# 01_GAP9_INTERFACE.net
KiCad netlist of a schematic drawn in Altium Designer
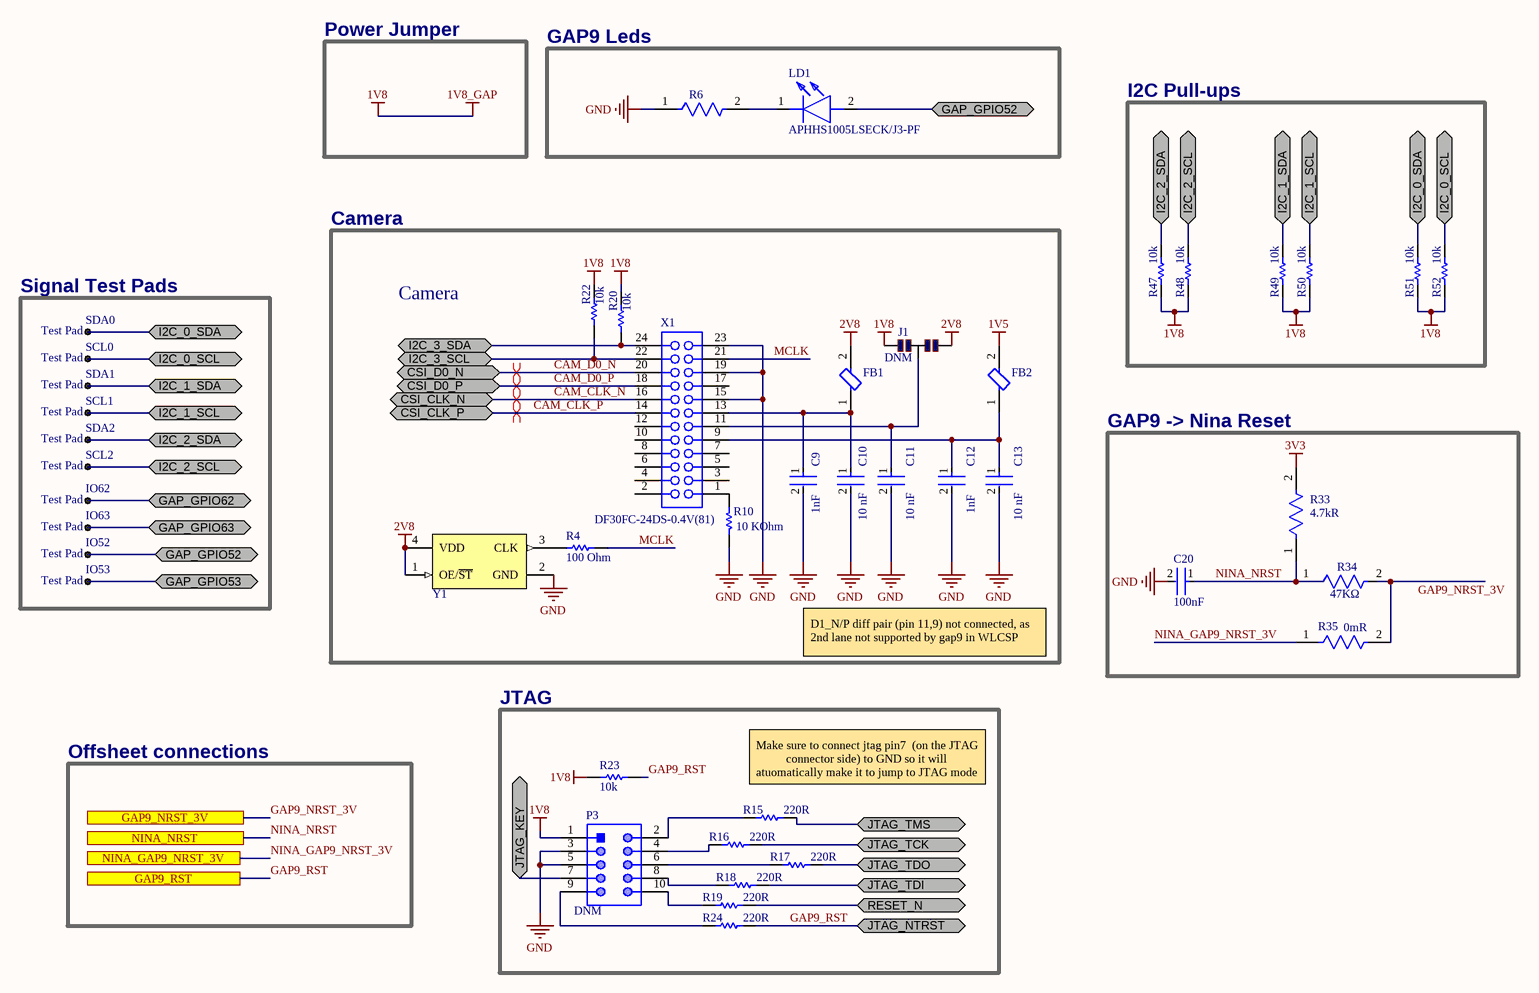
[diagram p0: 01_GAP9_INTERFACE.SchDoc]

(export (version "E")
  (design (tool "Eeschema 10.0.6"))
  (components
    (comp (ref "C9")
      (value "1nF")
      (footprint "FP-GRM155-0_05-IPC_B")
      (description "Chip Multilayer Ceramic Capacitors for General Purpose, 0402, 1000pF, C0G, 30ppm/°C, 5%, 50V")
      (fields (field (name "TOLERANCE") "5%") (field (name "VOLTAGE") "50V"))
      (libsource (lib "Altium Content Vault") (part "02cd4be3c70576c341d710602a673aa"))
    )
    (comp (ref "C10")
      (value "CC0402KRX7R7BB103")
      (footprint "FP-CC0402-MFG")
      (description "CAP CER 10000PF 16V X7R 0402")
      (fields
        (field (name "CAPACITANCE") "10 nF")
        (field (name "TOLERANCE") "0.1")
        (field (name "MANUFACTURER") "YAGEO")
      )
      (libsource (lib "Altium Content Vault") (part "11868f565c42a9108669ba33697ecf6"))
    )
    (comp (ref "C11")
      (value "CC0402KRX7R7BB103")
      (footprint "FP-CC0402-MFG")
      (description "CAP CER 10000PF 16V X7R 0402")
      (fields
        (field (name "CAPACITANCE") "10 nF")
        (field (name "TOLERANCE") "0.1")
        (field (name "MANUFACTURER") "YAGEO")
      )
      (libsource (lib "Altium Content Vault") (part "11868f565c42a9108669ba33697ecf6"))
    )
    (comp (ref "C12")
      (value "1nF")
      (footprint "FP-GRM155-0_05-IPC_B")
      (description "Chip Multilayer Ceramic Capacitors for General Purpose, 0402, 1000pF, C0G, 30ppm/°C, 5%, 50V")
      (fields (field (name "TOLERANCE") "5%") (field (name "VOLTAGE") "50V"))
      (libsource (lib "Altium Content Vault") (part "02cd4be3c70576c341d710602a673aa"))
    )
    (comp (ref "C13")
      (value "CC0402KRX7R7BB103")
      (footprint "FP-CC0402-MFG")
      (description "CAP CER 10000PF 16V X7R 0402")
      (fields
        (field (name "CAPACITANCE") "10 nF")
        (field (name "TOLERANCE") "0.1")
        (field (name "MANUFACTURER") "YAGEO")
      )
      (libsource (lib "Altium Content Vault") (part "11868f565c42a9108669ba33697ecf6"))
    )
    (comp (ref "C20")
      (value "100nF")
      (footprint "FP-C1005-050-0_05-MFG")
      (description "Multilayer Ceramic Capacitors 100nF ±10% 25V X5R SMD 0402")
      (fields (field (name "TOLERANCE") "10%") (field (name "VOLTAGE") "25V"))
      (libsource (lib "Altium Content Vault") (part "b4654b650e69147ec39a6b967a45e02"))
    )
    (comp (ref "FB1")
      (value "BLM18HE152SN1D")
      (footprint "FP-BLM18-0_15-t0_8-IPC_C")
      (description "Chip Ferrite Bead, 0603, 1500Ω @ 100MHz, 0.5Ω, 25%, 500mA")
      (fields (field (name "TOLERANCE") "25%"))
      (libsource (lib "Altium Content Vault") (part "5f30dd21d616792df468990f7003faa"))
    )
    (comp (ref "FB2")
      (value "BLM18HE152SN1D")
      (footprint "FP-BLM18-0_15-t0_8-IPC_C")
      (description "Chip Ferrite Bead, 0603, 1500Ω @ 100MHz, 0.5Ω, 25%, 500mA")
      (fields (field (name "TOLERANCE") "25%"))
      (libsource (lib "Altium Content Vault") (part "5f30dd21d616792df468990f7003faa"))
    )
    (comp (ref "IO52")
      (value "Test Pad")
      (footprint "Pad-1.5mm")
      (description "1mm SMT Test Pad")
      (libsource (lib "gap9_deck") (part "CMP-01283-1"))
    )
    (comp (ref "IO53")
      (value "Test Pad")
      (footprint "Pad-1.5mm")
      (description "1mm SMT Test Pad")
      (libsource (lib "gap9_deck") (part "CMP-01283-1"))
    )
    (comp (ref "IO62")
      (value "Test Pad")
      (footprint "Pad-1.5mm")
      (description "1mm SMT Test Pad")
      (libsource (lib "gap9_deck") (part "CMP-01283-1"))
    )
    (comp (ref "IO63")
      (value "Test Pad")
      (footprint "Pad-1.5mm")
      (description "1mm SMT Test Pad")
      (libsource (lib "gap9_deck") (part "CMP-01283-1"))
    )
    (comp (ref "J1")
      (value "DNM")
      (footprint "Jumper 3 pins")
      (description "Solder Jumper 3 Pads")
      (libsource (lib "ETHZ Vault") (part "Solder Jumper 3-pads"))
    )
    (comp (ref "LD1")
      (value "APHHS1005LSECK/J3-PF")
      (footprint "SamacSys:APHHS1005LSECKJ3PF")
      (description "LED")
      (fields (field (name "MOUSER PART NUMBER") "604-APHHS1005LSECKJ3"))
      (libsource (lib "*") (part "APHHS1005LSECK_J3-PF"))
    )
    (comp (ref "P3")
      (value "DNM")
      (footprint "Crazyflie:2x10Pin_Horizontal_50mil")
      (description "2x10 Pin 50mil Header")
      (libsource (lib "Crazyflie") (part "CF_JTAG_Header"))
    )
    (comp (ref "R4")
      (value "100 Ohm")
      (footprint "RESC1005X40X25LL05T05")
      (description "Chip Resistor, 100 Ohm, +/- 1%, 100 mW, -55 to 155 degC, 0402 (1005 Metric), RoHS, Tape and Reel")
      (fields (field (name "MANUFACTURER") "Basic Passives") (field (name "TOLERANCE") "1%"))
      (libsource (lib "Altium Content Vault") (part "RES-2"))
    )
    (comp (ref "R6")
      (value "RC0201JR-070RL")
      (footprint "FP-RC_L0201-MFG")
      (description "RES SMD 0 OHM JUMPER 1/20W 0201")
      (fields
        (field (name "OCTOPART") "https://octopart.com/rc0201jr-070rl-yageo-43171986")
        (field (name "MANUFACTURER") "Yageo")
      )
      (libsource (lib "Altium Content Vault") (part "1029c3af85768c4190bb7ad29bc67b5"))
    )
    (comp (ref "R10")
      (value "10 KOhm")
      (footprint "RESC1005X40X25NL05T05")
      (description "Chip Resistor, 10 KOhm, +/- 1%, 100 mW, -55 to 155 degC, 0402 (1005 Metric), RoHS, Tape and Reel")
      (fields (field (name "MANUFACTURER") "Basic Passives") (field (name "TOLERANCE") "1%"))
      (libsource (lib "Altium Content Vault") (part "CMP-2002-00607-3"))
    )
    (comp (ref "R15")
      (value "220R")
      (footprint "RESC0603X28X15ML05T05")
      (fields (field (name "MANUFACTURER") "Vishay Dale") (field (name "PART NUMBER") "CRCW0201220RFKED"))
      (libsource (lib "Altium Content Vault") (part "RES"))
    )
    (comp (ref "R16")
      (value "220R")
      (footprint "RESC0603X28X15ML05T05")
      (fields (field (name "MANUFACTURER") "Vishay Dale") (field (name "PART NUMBER") "CRCW0201220RFKED"))
      (libsource (lib "Altium Content Vault") (part "RES"))
    )
    (comp (ref "R17")
      (value "220R")
      (footprint "RESC0603X28X15ML05T05")
      (fields (field (name "MANUFACTURER") "Vishay Dale") (field (name "PART NUMBER") "CRCW0201220RFKED"))
      (libsource (lib "Altium Content Vault") (part "RES"))
    )
    (comp (ref "R18")
      (value "220R")
      (footprint "RESC0603X28X15ML05T05")
      (fields (field (name "MANUFACTURER") "Vishay Dale") (field (name "PART NUMBER") "CRCW0201220RFKED"))
      (libsource (lib "Altium Content Vault") (part "RES"))
    )
    (comp (ref "R19")
      (value "220R")
      (footprint "RESC0603X28X15ML05T05")
      (fields (field (name "MANUFACTURER") "Vishay Dale") (field (name "PART NUMBER") "CRCW0201220RFKED"))
      (libsource (lib "Altium Content Vault") (part "RES"))
    )
    (comp (ref "R20")
      (value "10k")
      (footprint "RESC0603X28X15LL05T05")
      (fields (field (name "MANUFACTURER") "Vishay Dale") (field (name "PART NUMBER") "CRCW020110K0FNED"))
      (libsource (lib "Altium Content Vault") (part "RES"))
    )
    (comp (ref "R22")
      (value "10k")
      (footprint "RESC0603X28X15LL05T05")
      (fields (field (name "MANUFACTURER") "Vishay Dale") (field (name "PART NUMBER") "CRCW020110K0FNED"))
      (libsource (lib "Altium Content Vault") (part "RES"))
    )
    (comp (ref "R23")
      (value "10k")
      (footprint "RESC0603X28X15LL05T05")
      (fields (field (name "MANUFACTURER") "Vishay Dale") (field (name "PART NUMBER") "CRCW020110K0FNED"))
      (libsource (lib "Altium Content Vault") (part "RES"))
    )
    (comp (ref "R24")
      (value "220R")
      (footprint "RESC0603X28X15ML05T05")
      (fields (field (name "MANUFACTURER") "Vishay Dale") (field (name "PART NUMBER") "CRCW0201220RFKED"))
      (libsource (lib "Altium Content Vault") (part "RES"))
    )
    (comp (ref "R33")
      (value "4.7kR")
      (footprint "FP-CRCW0402-e3-IPC_B")
      (description "RES Thick Film, 4.7kΩ, 1%, 0.063W, 100ppm/°C, 0402")
      (fields (field (name "TOLERANCE") "1%") (field (name "Comment") "CRCW04024K70FKED"))
      (libsource (lib "Altium Content Vault") (part "1029c3af85768c4190bb7ad29bc67b5"))
    )
    (comp (ref "R34")
      (value "47KΩ")
      (footprint "FP-CRGCQ0402-IPC_C")
      (description "CRGCQ0402 47KΩ 1% ±100ppm/°C 50V")
      (fields
        (field (name "OCTOPART") "https://octopart.com/crgcq0402f47k-te+connectivity-91017973")
        (field (name "TOLERANCE") "0.01")
      )
      (libsource (lib "Altium Content Vault") (part "1029c3af85768c4190bb7ad29bc67b5"))
    )
    (comp (ref "R35")
      (value "0mR")
      (footprint "FP-CRCW0402-e3-IPC_C")
      (description "RES Thick Film, 0Ω, 0.063W, 0402")
      (fields (field (name "TOLERANCE") "5%") (field (name "Comment") "CRCW04020000Z0ED"))
      (libsource (lib "Altium Content Vault") (part "1029c3af85768c4190bb7ad29bc67b5"))
    )
    (comp (ref "R47")
      (value "10k")
      (footprint "RESC0603X28X15LL05T05")
      (fields (field (name "MANUFACTURER") "Vishay Dale") (field (name "PART NUMBER") "CRCW020110K0FNED"))
      (libsource (lib "Altium Content Vault") (part "RES"))
    )
    (comp (ref "R48")
      (value "10k")
      (footprint "RESC0603X28X15LL05T05")
      (fields (field (name "MANUFACTURER") "Vishay Dale") (field (name "PART NUMBER") "CRCW020110K0FNED"))
      (libsource (lib "Altium Content Vault") (part "RES"))
    )
    (comp (ref "R49")
      (value "10k")
      (footprint "RESC0603X28X15LL05T05")
      (fields (field (name "MANUFACTURER") "Vishay Dale") (field (name "PART NUMBER") "CRCW020110K0FNED"))
      (libsource (lib "Altium Content Vault") (part "RES"))
    )
    (comp (ref "R50")
      (value "10k")
      (footprint "RESC0603X28X15LL05T05")
      (fields (field (name "MANUFACTURER") "Vishay Dale") (field (name "PART NUMBER") "CRCW020110K0FNED"))
      (libsource (lib "Altium Content Vault") (part "RES"))
    )
    (comp (ref "R51")
      (value "10k")
      (footprint "RESC0603X28X15LL05T05")
      (fields (field (name "MANUFACTURER") "Vishay Dale") (field (name "PART NUMBER") "CRCW020110K0FNED"))
      (libsource (lib "Altium Content Vault") (part "RES"))
    )
    (comp (ref "R52")
      (value "10k")
      (footprint "RESC0603X28X15LL05T05")
      (fields (field (name "MANUFACTURER") "Vishay Dale") (field (name "PART NUMBER") "CRCW020110K0FNED"))
      (libsource (lib "Altium Content Vault") (part "RES"))
    )
    (comp (ref "SCL0")
      (value "Test Pad")
      (footprint "Pad-1.5mm")
      (description "1mm SMT Test Pad")
      (libsource (lib "gap9_deck") (part "CMP-01283-1"))
    )
    (comp (ref "SCL1")
      (value "Test Pad")
      (footprint "Pad-1.5mm")
      (description "1mm SMT Test Pad")
      (libsource (lib "gap9_deck") (part "CMP-01283-1"))
    )
    (comp (ref "SCL2")
      (value "Test Pad")
      (footprint "Pad-1.5mm")
      (description "1mm SMT Test Pad")
      (libsource (lib "gap9_deck") (part "CMP-01283-1"))
    )
    (comp (ref "SDA0")
      (value "Test Pad")
      (footprint "Pad-1.5mm")
      (description "1mm SMT Test Pad")
      (libsource (lib "gap9_deck") (part "CMP-01283-1"))
    )
    (comp (ref "SDA1")
      (value "Test Pad")
      (footprint "Pad-1.5mm")
      (description "1mm SMT Test Pad")
      (libsource (lib "gap9_deck") (part "CMP-01283-1"))
    )
    (comp (ref "SDA2")
      (value "Test Pad")
      (footprint "Pad-1.5mm")
      (description "1mm SMT Test Pad")
      (libsource (lib "gap9_deck") (part "CMP-01283-1"))
    )
    (comp (ref "X1")
      (value "DF30FC-24DS-0.4V(81)")
      (footprint "DF30FC-24DS-0.4V(81)")
      (libsource (lib "ETHZ Vault") (part "CON-2x12-Female"))
    )
    (comp (ref "Y1")
      (value "KC2520K25.0000C1GE00")
      (footprint "AB-24.000MAGE-T")
      (description "OSCILLATOR XO 25.000MHZ CMOS SMD")
      (fields (field (name "MANUFACTURER") "AVX-Corp-Kyocera-Corp"))
      (libsource (lib "altium-import") (part "root_0_SiT8008_"))
    )
  )
  (nets
    (net (code "1") (name "/CAM_CLK_N") (class "Default")
      (node (ref "X1") (pin "16") (pinfunction "16_16") (pintype "passive"))
    )
    (net (code "2") (name "/CAM_CLK_P") (class "Default")
      (node (ref "X1") (pin "14") (pinfunction "14_14") (pintype "passive"))
    )
    (net (code "3") (name "/CAM_D0_N") (class "Default")
      (node (ref "X1") (pin "20") (pinfunction "20_20") (pintype "passive"))
    )
    (net (code "4") (name "/CAM_D0_P") (class "Default")
      (node (ref "X1") (pin "18") (pinfunction "18_18") (pintype "passive"))
    )
    (net (code "5") (name "/GAP9_NRST_3V") (class "Default")
      (node (ref "R34") (pin "2") (pinfunction "2_2") (pintype "passive"))
      (node (ref "R35") (pin "2") (pinfunction "2_2") (pintype "passive"))
    )
    (net (code "6") (name "/GAP9_RST") (class "Default")
      (node (ref "R23") (pin "2") (pinfunction "2_2") (pintype "passive"))
      (node (ref "R24") (pin "2") (pinfunction "2_2") (pintype "passive"))
    )
    (net (code "7") (name "/GAP_GPIO52") (class "Default")
      (node (ref "IO52") (pin "1") (pinfunction "1_1") (pintype "passive"))
      (node (ref "LD1") (pin "2") (pinfunction "A_2") (pintype "passive"))
    )
    (net (code "8") (name "/GAP_GPIO53") (class "Default")
      (node (ref "IO53") (pin "1") (pinfunction "1_1") (pintype "passive"))
    )
    (net (code "9") (name "/GAP_GPIO62") (class "Default")
      (node (ref "IO62") (pin "1") (pinfunction "1_1") (pintype "passive"))
    )
    (net (code "10") (name "/GAP_GPIO63") (class "Default")
      (node (ref "IO63") (pin "1") (pinfunction "1_1") (pintype "passive"))
    )
    (net (code "11") (name "/I2C_0_SCL") (class "Default")
      (node (ref "R52") (pin "2") (pinfunction "2_2") (pintype "passive"))
      (node (ref "SCL0") (pin "1") (pinfunction "1_1") (pintype "passive"))
    )
    (net (code "12") (name "/I2C_0_SDA") (class "Default")
      (node (ref "R51") (pin "2") (pinfunction "2_2") (pintype "passive"))
      (node (ref "SDA0") (pin "1") (pinfunction "1_1") (pintype "passive"))
    )
    (net (code "13") (name "/I2C_1_SCL") (class "Default")
      (node (ref "R50") (pin "2") (pinfunction "2_2") (pintype "passive"))
      (node (ref "SCL1") (pin "1") (pinfunction "1_1") (pintype "passive"))
    )
    (net (code "14") (name "/I2C_1_SDA") (class "Default")
      (node (ref "R49") (pin "2") (pinfunction "2_2") (pintype "passive"))
      (node (ref "SDA1") (pin "1") (pinfunction "1_1") (pintype "passive"))
    )
    (net (code "15") (name "/I2C_2_SCL") (class "Default")
      (node (ref "R48") (pin "2") (pinfunction "2_2") (pintype "passive"))
      (node (ref "SCL2") (pin "1") (pinfunction "1_1") (pintype "passive"))
    )
    (net (code "16") (name "/I2C_2_SDA") (class "Default")
      (node (ref "R47") (pin "2") (pinfunction "2_2") (pintype "passive"))
      (node (ref "SDA2") (pin "1") (pinfunction "1_1") (pintype "passive"))
    )
    (net (code "17") (name "/I2C_3_SCL") (class "Default")
      (node (ref "R22") (pin "1") (pinfunction "1_1") (pintype "passive"))
      (node (ref "X1") (pin "22") (pinfunction "22_22") (pintype "passive"))
    )
    (net (code "18") (name "/I2C_3_SDA") (class "Default")
      (node (ref "R20") (pin "1") (pinfunction "1_1") (pintype "passive"))
      (node (ref "X1") (pin "24") (pinfunction "24_24") (pintype "passive"))
    )
    (net (code "19") (name "/JTAG_KEY") (class "Default")
      (node (ref "P3") (pin "7") (pinfunction "7_7") (pintype "passive"))
    )
    (net (code "20") (name "/JTAG_TCK") (class "Default")
      (node (ref "R16") (pin "2") (pinfunction "2_2") (pintype "passive"))
    )
    (net (code "21") (name "/JTAG_TDI") (class "Default")
      (node (ref "R18") (pin "2") (pinfunction "2_2") (pintype "passive"))
    )
    (net (code "22") (name "/JTAG_TDO") (class "Default")
      (node (ref "R17") (pin "2") (pinfunction "2_2") (pintype "passive"))
    )
    (net (code "23") (name "/JTAG_TMS") (class "Default")
      (node (ref "R15") (pin "2") (pinfunction "2_2") (pintype "passive"))
    )
    (net (code "24") (name "/MCLK") (class "Default")
      (node (ref "R4") (pin "1") (pinfunction "1_1") (pintype "passive"))
      (node (ref "X1") (pin "21") (pinfunction "21_21") (pintype "passive"))
    )
    (net (code "25") (name "/NINA_GAP9_NRST_3V") (class "Default")
      (node (ref "R35") (pin "1") (pinfunction "1_1") (pintype "passive"))
    )
    (net (code "26") (name "/NINA_NRST") (class "Default")
      (node (ref "C20") (pin "1") (pinfunction "1_1") (pintype "passive"))
      (node (ref "R33") (pin "1") (pinfunction "1_1") (pintype "passive"))
      (node (ref "R34") (pin "1") (pinfunction "1_1") (pintype "passive"))
    )
    (net (code "27") (name "/RESET_N") (class "Default")
      (node (ref "R19") (pin "2") (pinfunction "2_2") (pintype "passive"))
    )
    (net (code "28") (name "1V5") (class "Default")
      (node (ref "FB2") (pin "2") (pinfunction "2_2") (pintype "passive"))
    )
    (net (code "29") (name "1V8") (class "Default")
      (node (ref "J1") (pin "1") (pinfunction "1_1") (pintype "passive"))
      (node (ref "P3") (pin "1") (pinfunction "1_1") (pintype "passive"))
      (node (ref "R20") (pin "2") (pinfunction "2_2") (pintype "passive"))
      (node (ref "R22") (pin "2") (pinfunction "2_2") (pintype "passive"))
      (node (ref "R23") (pin "1") (pinfunction "1_1") (pintype "passive"))
      (node (ref "R47") (pin "1") (pinfunction "1_1") (pintype "passive"))
      (node (ref "R48") (pin "1") (pinfunction "1_1") (pintype "passive"))
      (node (ref "R49") (pin "1") (pinfunction "1_1") (pintype "passive"))
      (node (ref "R50") (pin "1") (pinfunction "1_1") (pintype "passive"))
      (node (ref "R51") (pin "1") (pinfunction "1_1") (pintype "passive"))
      (node (ref "R52") (pin "1") (pinfunction "1_1") (pintype "passive"))
    )
    (net (code "30") (name "2V8") (class "Default")
      (node (ref "FB1") (pin "2") (pinfunction "2_2") (pintype "passive"))
      (node (ref "J1") (pin "3") (pinfunction "3_3") (pintype "passive"))
      (node (ref "Y1") (pin "1") (pinfunction "OE/~{ST}_1") (pintype "input"))
      (node (ref "Y1") (pin "4") (pinfunction "VDD_4") (pintype "power_in"))
    )
    (net (code "31") (name "3V3") (class "Default")
      (node (ref "R33") (pin "2") (pinfunction "2_2") (pintype "passive"))
    )
    (net (code "32") (name "GND") (class "Default")
      (node (ref "C10") (pin "2") (pinfunction "2_2") (pintype "passive"))
      (node (ref "C11") (pin "2") (pinfunction "2_2") (pintype "passive"))
      (node (ref "C12") (pin "2") (pinfunction "2_2") (pintype "passive"))
      (node (ref "C13") (pin "2") (pinfunction "2_2") (pintype "passive"))
      (node (ref "C20") (pin "2") (pinfunction "2_2") (pintype "passive"))
      (node (ref "C9") (pin "2") (pinfunction "2_2") (pintype "passive"))
      (node (ref "P3") (pin "3") (pinfunction "3_3") (pintype "passive"))
      (node (ref "P3") (pin "5") (pinfunction "5_5") (pintype "passive"))
      (node (ref "R10") (pin "2") (pinfunction "2_2") (pintype "passive"))
      (node (ref "R6") (pin "1") (pinfunction "1_1") (pintype "passive"))
      (node (ref "X1") (pin "15") (pinfunction "15_15") (pintype "passive"))
      (node (ref "X1") (pin "19") (pinfunction "19_19") (pintype "passive"))
      (node (ref "X1") (pin "23") (pinfunction "23_23") (pintype "passive"))
      (node (ref "Y1") (pin "2") (pinfunction "GND_2") (pintype "power_in"))
    )
    (net (code "33") (name "Net-(C10-Pad1)") (class "Default")
      (node (ref "C10") (pin "1") (pinfunction "1_1") (pintype "passive"))
      (node (ref "C9") (pin "1") (pinfunction "1_1") (pintype "passive"))
      (node (ref "FB1") (pin "1") (pinfunction "1_1") (pintype "passive"))
      (node (ref "X1") (pin "13") (pinfunction "13_13") (pintype "passive"))
    )
    (net (code "34") (name "Net-(C11-Pad1)") (class "Default")
      (node (ref "C11") (pin "1") (pinfunction "1_1") (pintype "passive"))
      (node (ref "J1") (pin "2") (pinfunction "2_2") (pintype "passive"))
      (node (ref "X1") (pin "11") (pinfunction "11_11") (pintype "passive"))
    )
    (net (code "35") (name "Net-(C12-Pad1)") (class "Default")
      (node (ref "C12") (pin "1") (pinfunction "1_1") (pintype "passive"))
      (node (ref "C13") (pin "1") (pinfunction "1_1") (pintype "passive"))
      (node (ref "FB2") (pin "1") (pinfunction "1_1") (pintype "passive"))
      (node (ref "X1") (pin "9") (pinfunction "9_9") (pintype "passive"))
    )
    (net (code "36") (name "Net-(LD1-K)") (class "Default")
      (node (ref "LD1") (pin "1") (pinfunction "K_1") (pintype "passive"))
      (node (ref "R6") (pin "2") (pinfunction "2_2") (pintype "passive"))
    )
    (net (code "37") (name "Net-(P3-Pad2)") (class "Default")
      (node (ref "P3") (pin "2") (pinfunction "2_2") (pintype "passive"))
      (node (ref "R15") (pin "1") (pinfunction "1_1") (pintype "passive"))
    )
    (net (code "38") (name "Net-(P3-Pad4)") (class "Default")
      (node (ref "P3") (pin "4") (pinfunction "4_4") (pintype "passive"))
      (node (ref "R16") (pin "1") (pinfunction "1_1") (pintype "passive"))
    )
    (net (code "39") (name "Net-(P3-Pad6)") (class "Default")
      (node (ref "P3") (pin "6") (pinfunction "6_6") (pintype "passive"))
      (node (ref "R17") (pin "1") (pinfunction "1_1") (pintype "passive"))
    )
    (net (code "40") (name "Net-(P3-Pad8)") (class "Default")
      (node (ref "P3") (pin "8") (pinfunction "8_8") (pintype "passive"))
      (node (ref "R18") (pin "1") (pinfunction "1_1") (pintype "passive"))
    )
    (net (code "41") (name "Net-(P3-Pad9)") (class "Default")
      (node (ref "P3") (pin "9") (pinfunction "9_9") (pintype "passive"))
      (node (ref "R24") (pin "1") (pinfunction "1_1") (pintype "passive"))
    )
    (net (code "42") (name "Net-(P3-Pad10)") (class "Default")
      (node (ref "P3") (pin "10") (pinfunction "10_10") (pintype "passive"))
      (node (ref "R19") (pin "1") (pinfunction "1_1") (pintype "passive"))
    )
    (net (code "43") (name "Net-(R10-Pad1)") (class "Default")
      (node (ref "R10") (pin "1") (pinfunction "1_1") (pintype "passive"))
      (node (ref "X1") (pin "1") (pinfunction "1_1") (pintype "passive"))
    )
    (net (code "44") (name "Net-(Y1-CLK)") (class "Default")
      (node (ref "R4") (pin "2") (pinfunction "2_2") (pintype "passive"))
      (node (ref "Y1") (pin "3") (pinfunction "CLK_3") (pintype "output"))
    )
    (net (code "45") (name "unconnected-(X1-Pad2)") (class "Default")
      (node (ref "X1") (pin "2") (pinfunction "2_2") (pintype "passive"))
    )
    (net (code "46") (name "unconnected-(X1-Pad3)") (class "Default")
      (node (ref "X1") (pin "3") (pinfunction "3_3") (pintype "passive"))
    )
    (net (code "47") (name "unconnected-(X1-Pad4)") (class "Default")
      (node (ref "X1") (pin "4") (pinfunction "4_4") (pintype "passive"))
    )
    (net (code "48") (name "unconnected-(X1-Pad5)") (class "Default")
      (node (ref "X1") (pin "5") (pinfunction "5_5") (pintype "passive"))
    )
    (net (code "49") (name "unconnected-(X1-Pad6)") (class "Default")
      (node (ref "X1") (pin "6") (pinfunction "6_6") (pintype "passive"))
    )
    (net (code "50") (name "unconnected-(X1-Pad7)") (class "Default")
      (node (ref "X1") (pin "7") (pinfunction "7_7") (pintype "passive"))
    )
    (net (code "51") (name "unconnected-(X1-Pad8)") (class "Default")
      (node (ref "X1") (pin "8") (pinfunction "8_8") (pintype "passive"))
    )
    (net (code "52") (name "unconnected-(X1-Pad10)") (class "Default")
      (node (ref "X1") (pin "10") (pinfunction "10_10") (pintype "passive"))
    )
    (net (code "53") (name "unconnected-(X1-Pad12)") (class "Default")
      (node (ref "X1") (pin "12") (pinfunction "12_12") (pintype "passive"))
    )
    (net (code "54") (name "unconnected-(X1-Pad17)") (class "Default")
      (node (ref "X1") (pin "17") (pinfunction "17_17") (pintype "passive"))
    )
  )
)
